# BrushlessLampRoutes.net
KiCad netlist of a schematic drawn in EAGLE
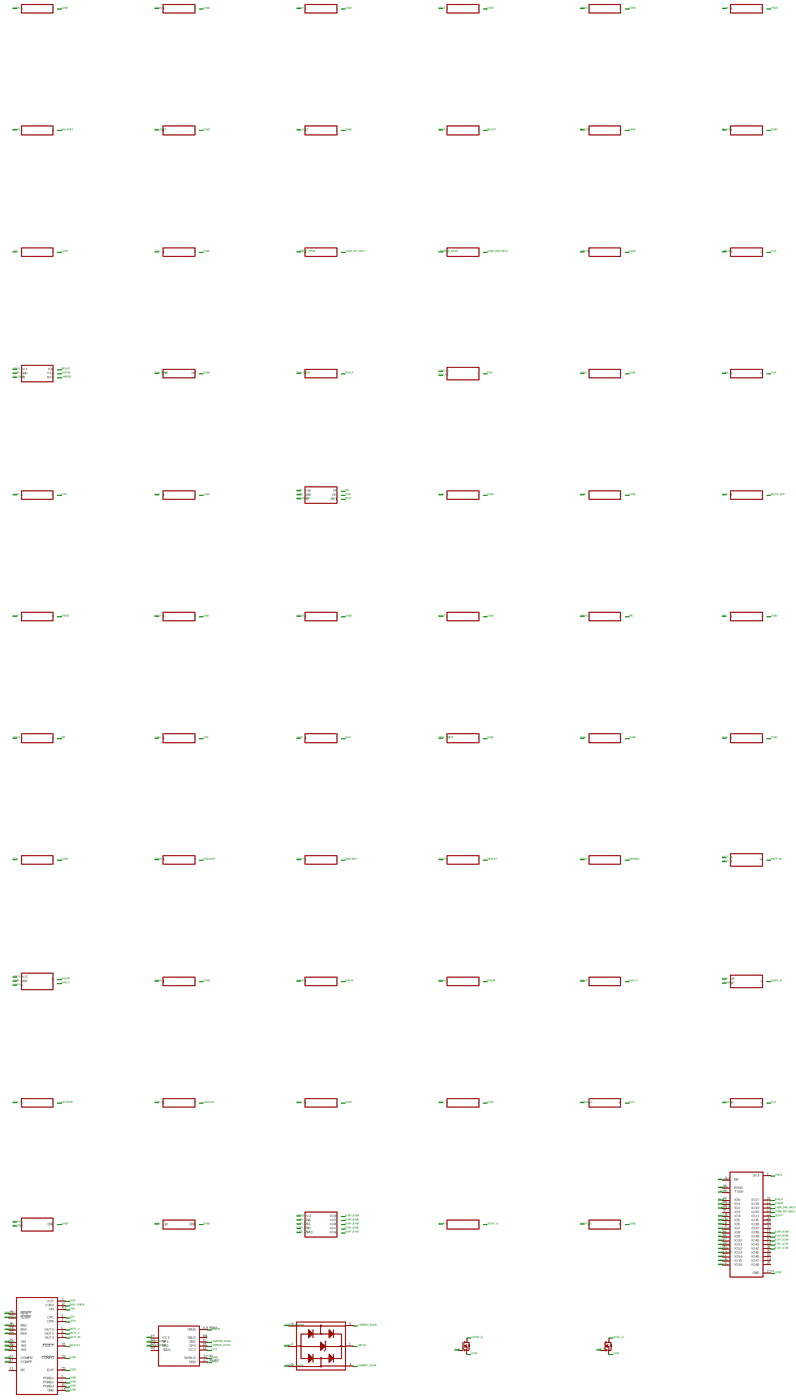
[diagram p0: schematic, sheet 1, overview]
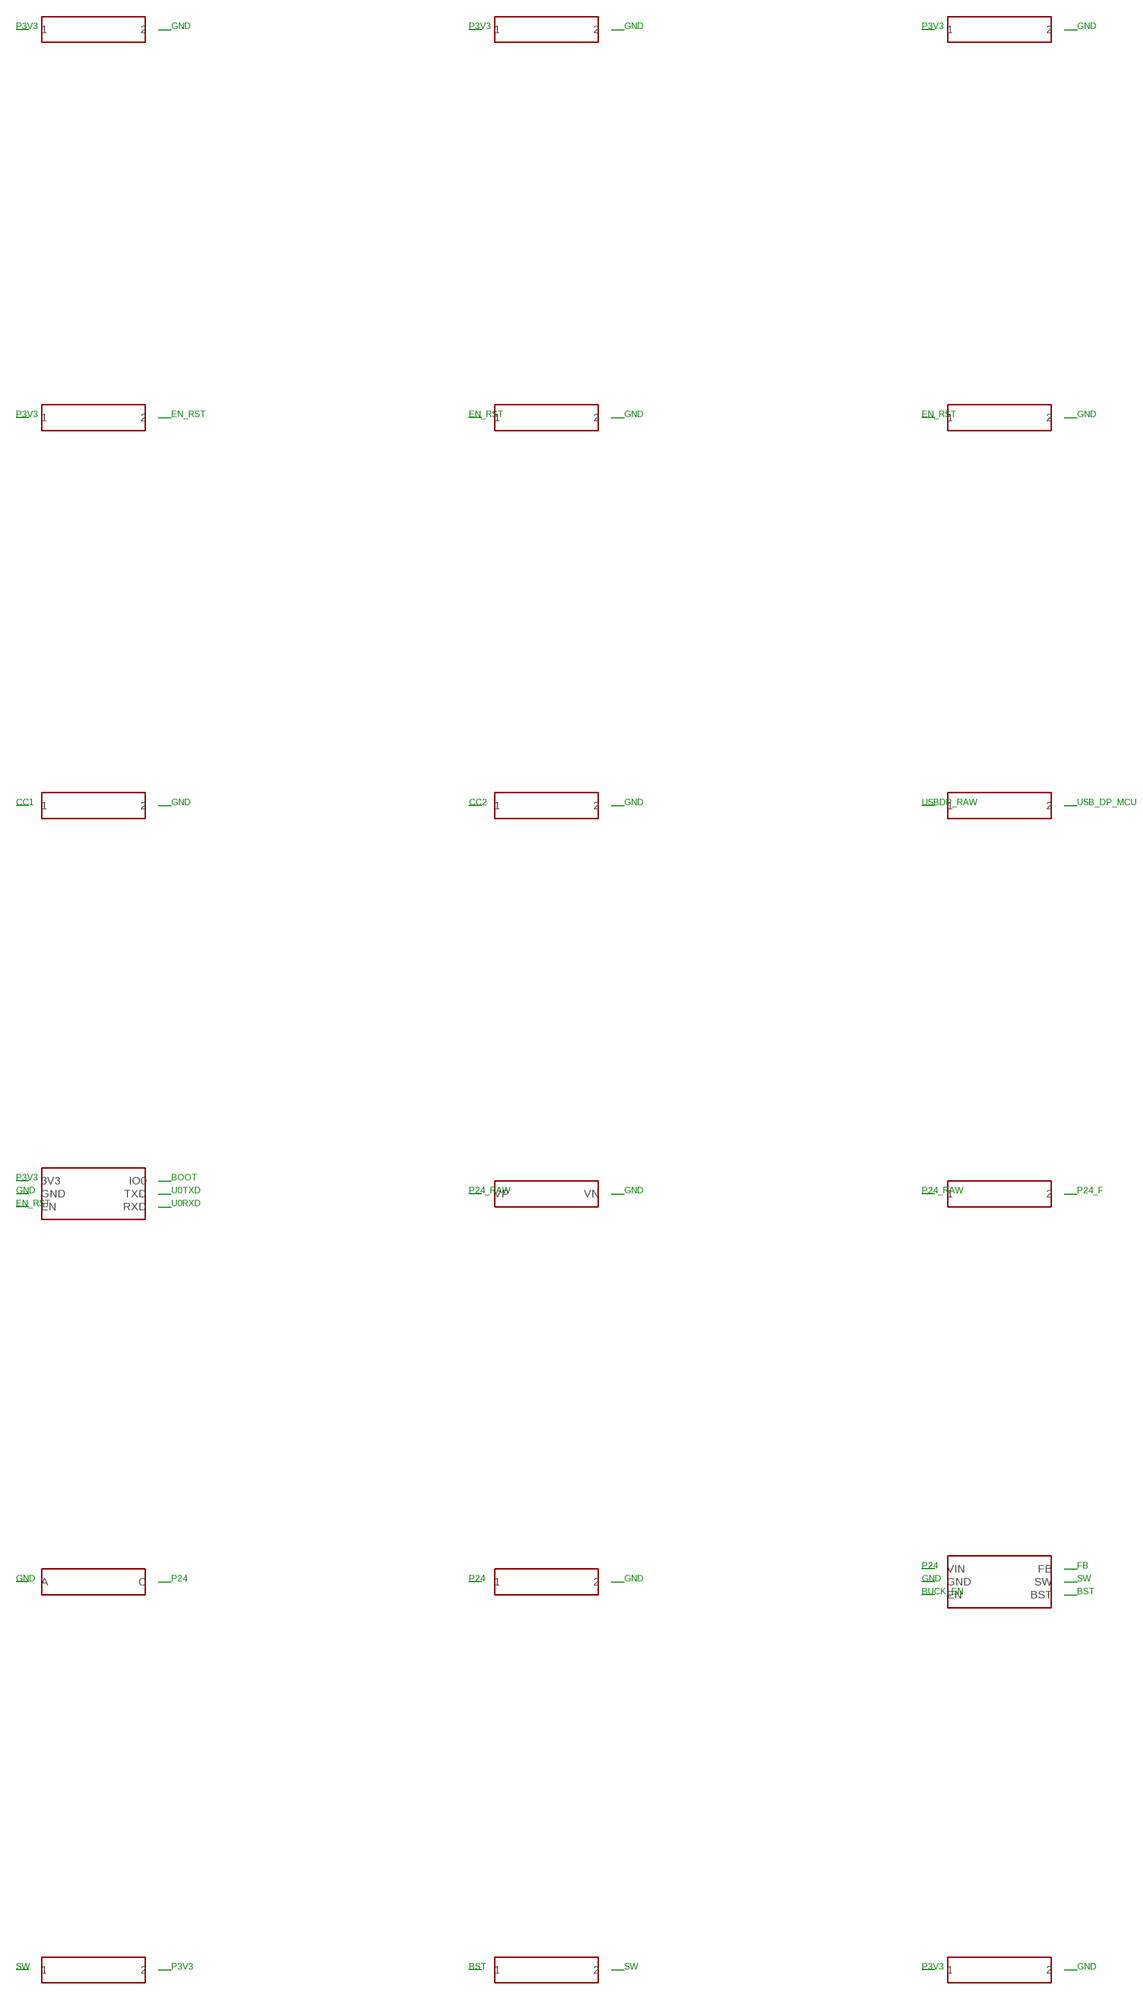
[diagram p1: schematic, sheet 1, part 1 of 4]
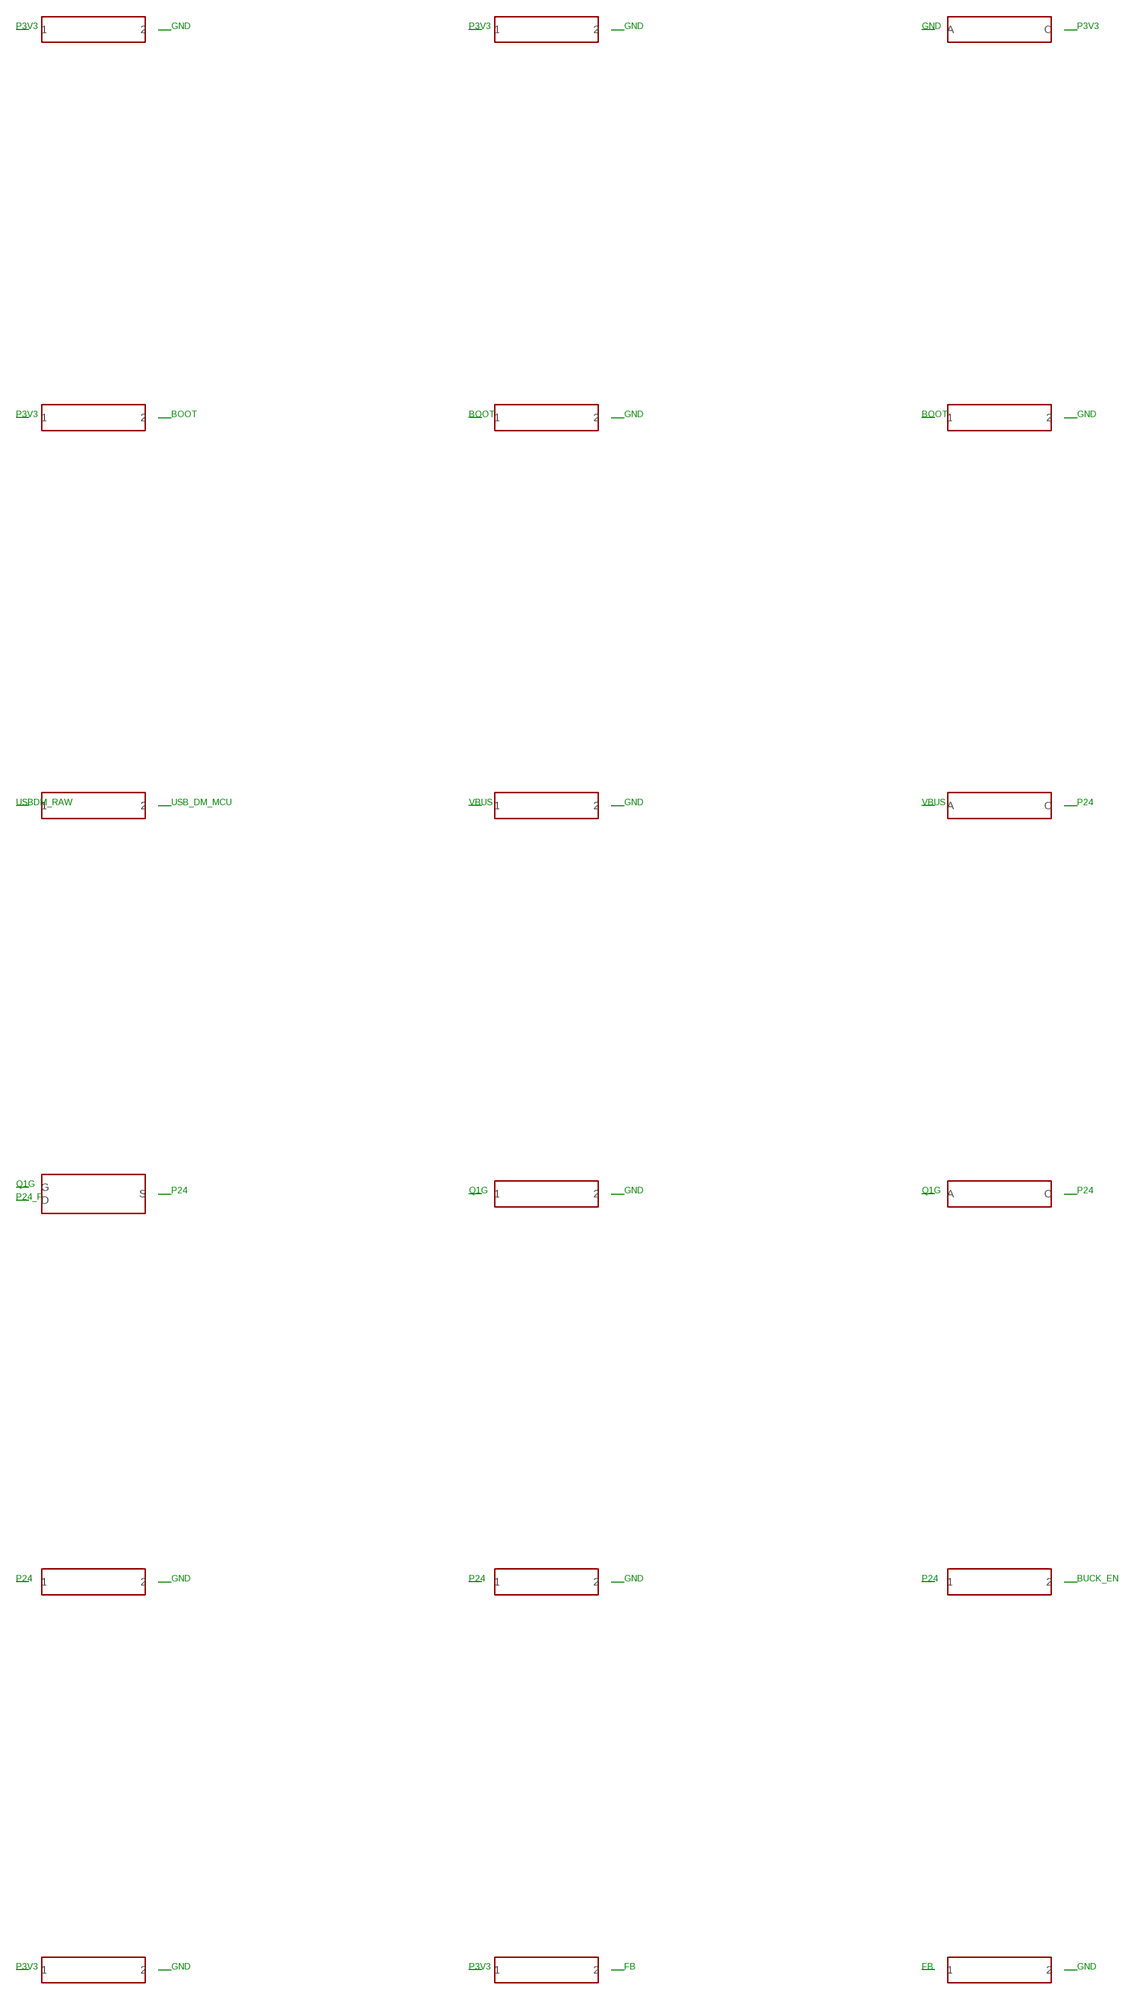
[diagram p2: schematic, sheet 1, part 2 of 4]
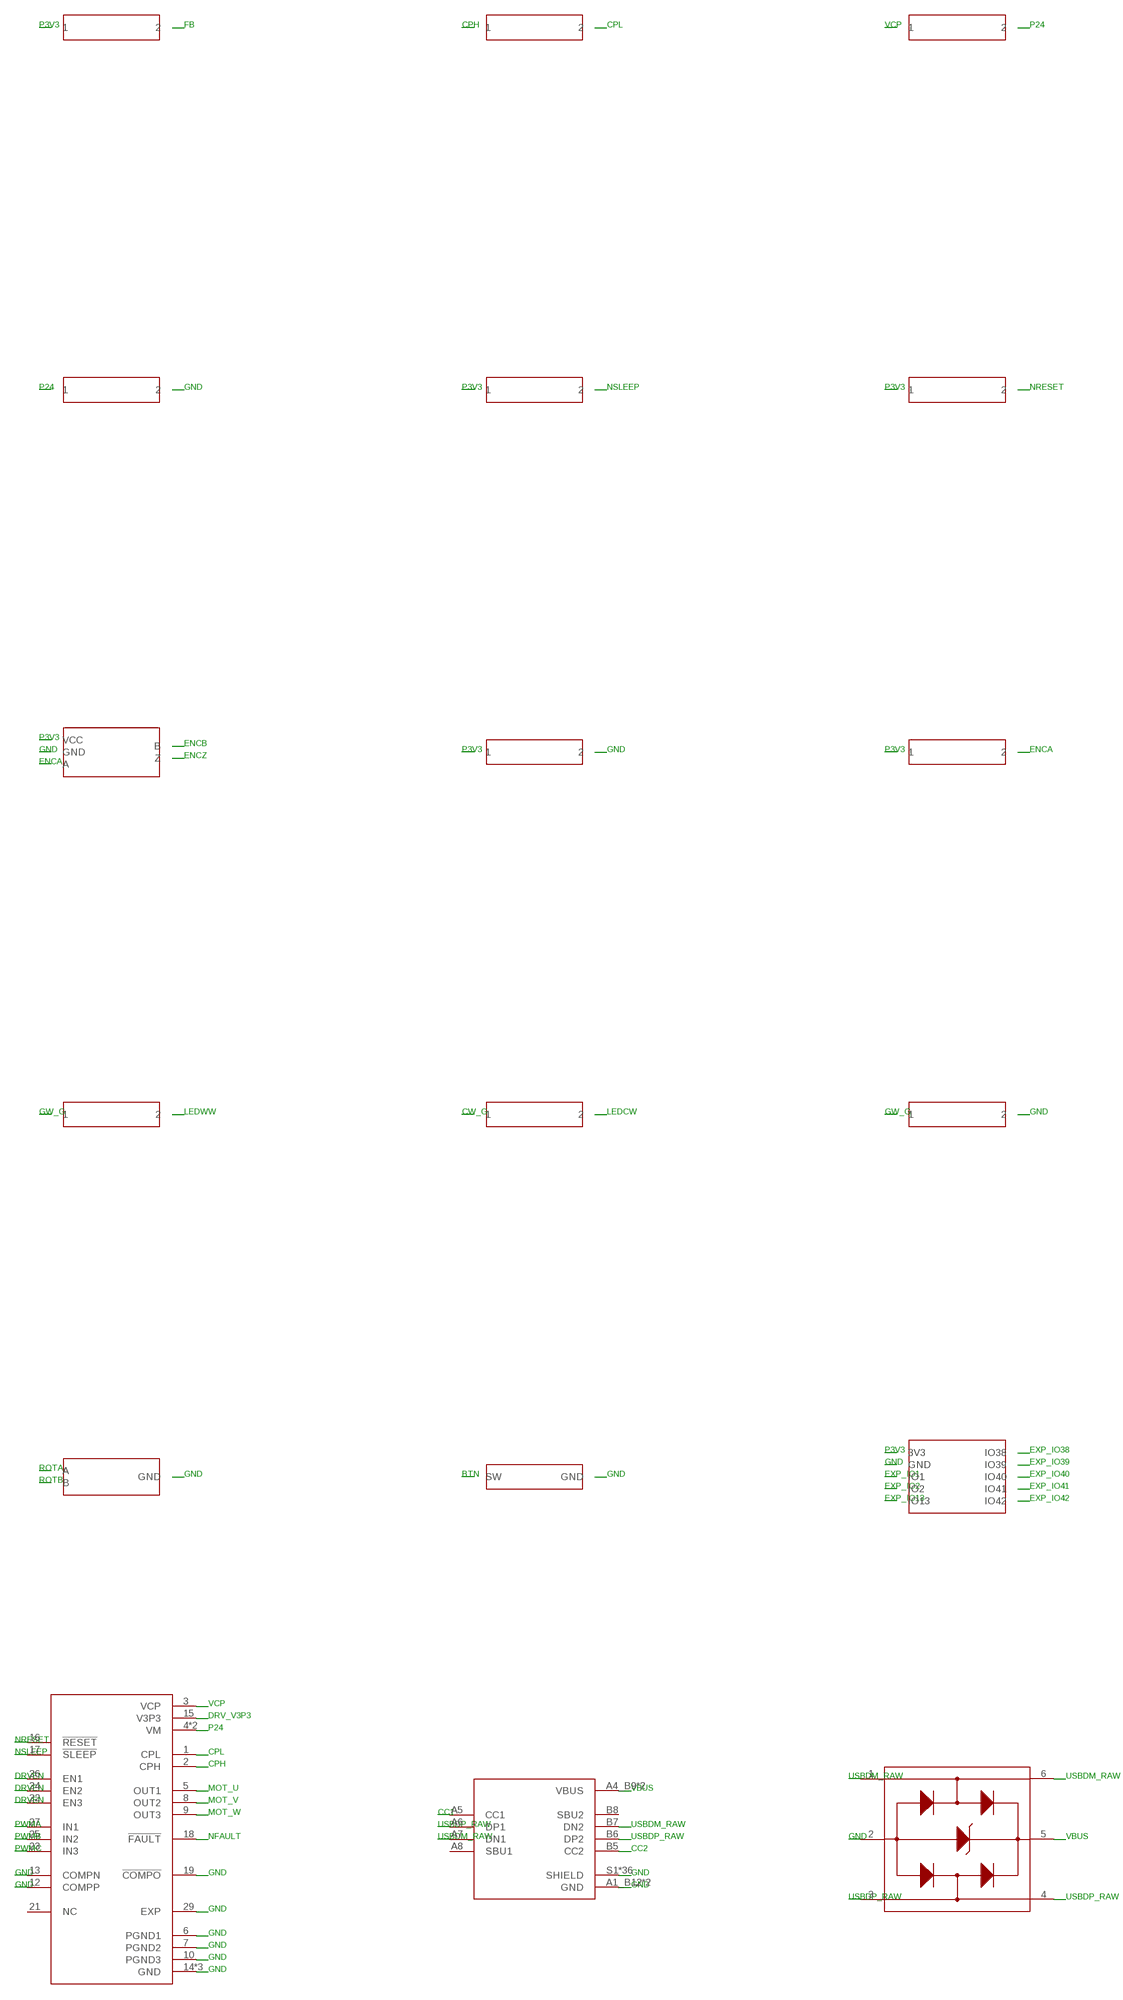
[diagram p3: schematic, sheet 1, part 3 of 4]
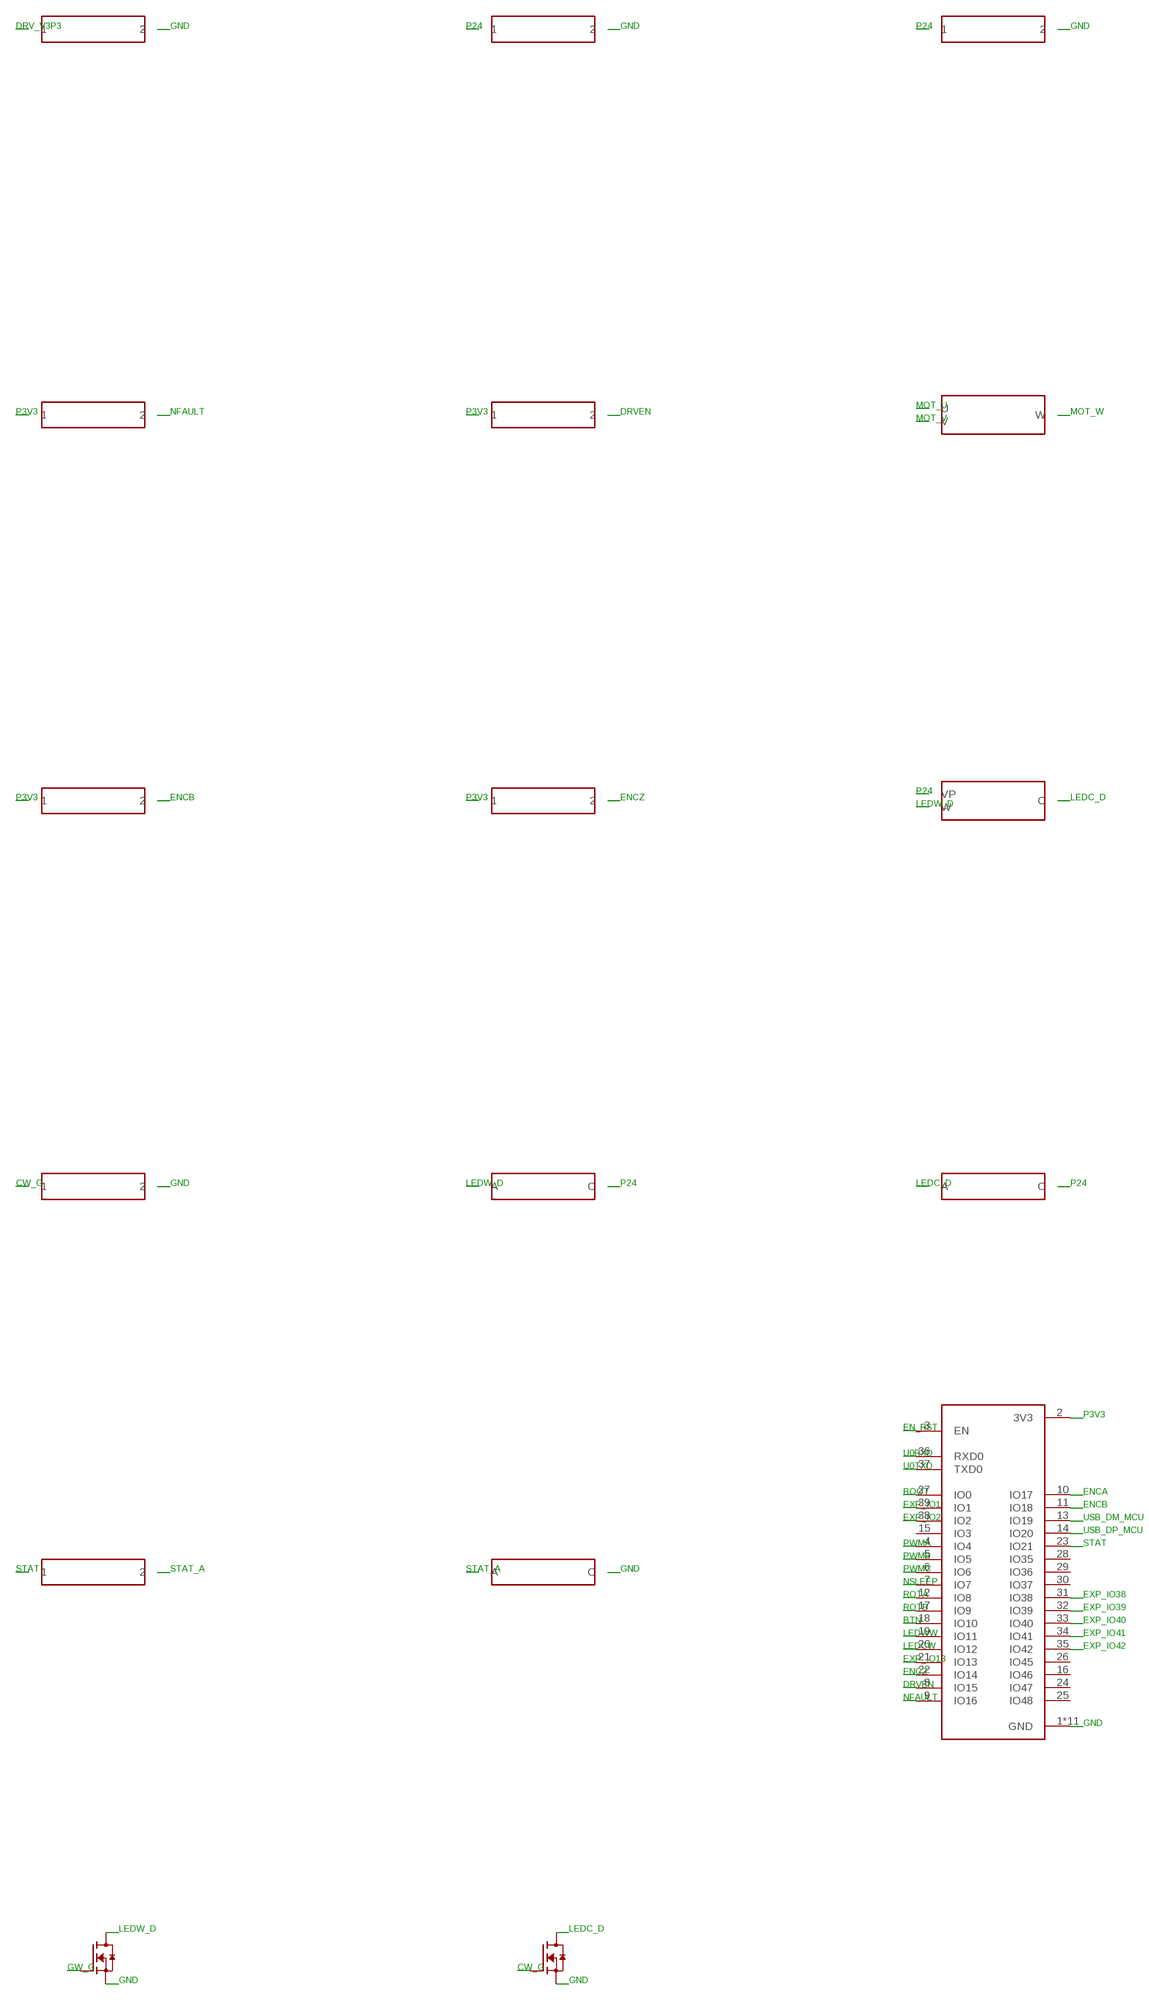
[diagram p4: schematic, sheet 1, part 4 of 4]

(export (version "E")
  (design (tool "Eeschema 10.0.6"))
  (components
    (comp (ref "C_BOOT")
      (value "100p")
      (footprint "eagle-import:0402")
      (libsource (lib "eagle-import") (part "CAP_0402"))
    )
    (comp (ref "C_BOOT_B")
      (value "100n")
      (footprint "eagle-import:0402")
      (libsource (lib "eagle-import") (part "CAP_0402"))
    )
    (comp (ref "C_CP")
      (value "10n")
      (footprint "eagle-import:0603")
      (libsource (lib "eagle-import") (part "CAP_0603"))
    )
    (comp (ref "C_EN")
      (value "1u")
      (footprint "eagle-import:0603")
      (libsource (lib "eagle-import") (part "CAP_0603"))
    )
    (comp (ref "C_FF")
      (value "22p")
      (footprint "eagle-import:0402")
      (libsource (lib "eagle-import") (part "CAP_0402"))
    )
    (comp (ref "C_IN1")
      (value "10u-50V")
      (footprint "eagle-import:1210")
      (libsource (lib "eagle-import") (part "CAP_1210"))
    )
    (comp (ref "C_IN2")
      (value "4.7u-50V")
      (footprint "eagle-import:1206")
      (libsource (lib "eagle-import") (part "CAP_1206"))
    )
    (comp (ref "C_IN_BULK")
      (value "100u-50V")
      (footprint "eagle-import:CAP_V")
      (libsource (lib "eagle-import") (part "CAP_V"))
    )
    (comp (ref "C_MCU1")
      (value "10u")
      (footprint "eagle-import:0805")
      (libsource (lib "eagle-import") (part "CAP_0805"))
    )
    (comp (ref "C_MCU2")
      (value "1u")
      (footprint "eagle-import:0603")
      (libsource (lib "eagle-import") (part "CAP_0603"))
    )
    (comp (ref "C_MCU3")
      (value "100n")
      (footprint "eagle-import:0402")
      (libsource (lib "eagle-import") (part "CAP_0402"))
    )
    (comp (ref "C_MCU4")
      (value "100n")
      (footprint "eagle-import:0402")
      (libsource (lib "eagle-import") (part "CAP_0402"))
    )
    (comp (ref "C_MCU_BULK")
      (value "470u")
      (footprint "eagle-import:CAP_D")
      (libsource (lib "eagle-import") (part "CAP_D"))
    )
    (comp (ref "C_OUT1")
      (value "22u")
      (footprint "eagle-import:0805")
      (libsource (lib "eagle-import") (part "CAP_0805"))
    )
    (comp (ref "C_OUT2")
      (value "22u")
      (footprint "eagle-import:0805")
      (libsource (lib "eagle-import") (part "CAP_0805"))
    )
    (comp (ref "C_SENS")
      (value "100n")
      (footprint "eagle-import:0402")
      (libsource (lib "eagle-import") (part "CAP_0402"))
    )
    (comp (ref "C_V3P3")
      (value "470n")
      (footprint "eagle-import:0603")
      (libsource (lib "eagle-import") (part "CAP_0603"))
    )
    (comp (ref "C_VBUS")
      (value "4.7u")
      (footprint "eagle-import:0603")
      (libsource (lib "eagle-import") (part "CAP_0603"))
    )
    (comp (ref "C_VCP")
      (value "100n")
      (footprint "eagle-import:0603")
      (libsource (lib "eagle-import") (part "CAP_0603"))
    )
    (comp (ref "C_VM1")
      (value "100n-50V")
      (footprint "eagle-import:0603")
      (libsource (lib "eagle-import") (part "CAP_0603"))
    )
    (comp (ref "C_VM2")
      (value "100n-50V")
      (footprint "eagle-import:0603")
      (libsource (lib "eagle-import") (part "CAP_0603"))
    )
    (comp (ref "C_VM_BULK")
      (value "100u-50V")
      (footprint "eagle-import:CAP_V")
      (libsource (lib "eagle-import") (part "CAP_V"))
    )
    (comp (ref "D_CLC")
      (value "clamp-DNP")
      (footprint "eagle-import:SOD323")
      (libsource (lib "eagle-import") (part "DIODE_SOD323"))
    )
    (comp (ref "D_CLW")
      (value "clamp-DNP")
      (footprint "eagle-import:SOD323")
      (libsource (lib "eagle-import") (part "DIODE_SOD323"))
    )
    (comp (ref "D_MCU")
      (value "ESD")
      (footprint "eagle-import:SOD323")
      (libsource (lib "eagle-import") (part "DIODE_SOD323"))
    )
    (comp (ref "D_OR_USB")
      (value "SS14")
      (footprint "eagle-import:SMA")
      (libsource (lib "eagle-import") (part "DIODE_SMA"))
    )
    (comp (ref "D_Q1")
      (value "10V-Zener")
      (footprint "eagle-import:SOD123")
      (libsource (lib "eagle-import") (part "DIODE_SOD123"))
    )
    (comp (ref "D_USB")
      (value "USBLC6-2SC6")
      (footprint "eagle-import:SOT95P280X145-6N")
      (fields (field (name "MF") "STMicroelectronics"))
      (libsource (lib "eagle-import") (part "USBLC6-2SC6"))
    )
    (comp (ref "F1")
      (value "2A")
      (footprint "eagle-import:FUSENANO2")
      (libsource (lib "eagle-import") (part "FUSE_NANO2"))
    )
    (comp (ref "J_BTN")
      (value "BUTTON")
      (footprint "eagle-import:XH2")
      (libsource (lib "eagle-import") (part "CONN_BTN_DS"))
    )
    (comp (ref "J_EXP")
      (value "GPIO-EXP")
      (footprint "eagle-import:HDR10")
      (libsource (lib "eagle-import") (part "CONN_EXP_DS"))
    )
    (comp (ref "J_KNOB")
      (value "KNOB")
      (footprint "eagle-import:XH3")
      (libsource (lib "eagle-import") (part "CONN_KNOB_DS"))
    )
    (comp (ref "J_LED")
      (value "CCT-STRIP")
      (footprint "eagle-import:XH3")
      (libsource (lib "eagle-import") (part "CONN_LED_DS"))
    )
    (comp (ref "J_MOTOR")
      (value "MOTOR")
      (footprint "eagle-import:SCREW3")
      (libsource (lib "eagle-import") (part "CONN_MOTOR_DS"))
    )
    (comp (ref "J_PROG")
      (value "UART-FALLBACK")
      (footprint "eagle-import:HDR6")
      (libsource (lib "eagle-import") (part "CONN_PROG_DS"))
    )
    (comp (ref "J_PWR")
      (value "24V-IN")
      (footprint "eagle-import:SCREW2")
      (libsource (lib "eagle-import") (part "CONN_PWR_DS"))
    )
    (comp (ref "J_SENSOR")
      (value "MT6701")
      (footprint "eagle-import:SCREW5")
      (libsource (lib "eagle-import") (part "CONN_SENSOR_DS"))
    )
    (comp (ref "J_USB")
      (value "TYPE-C-31-M-12")
      (footprint "eagle-import:HRO_TYPE-C-31-M-12")
      (fields (field (name "MF") "HRO Electronics Co., Ltd."))
      (libsource (lib "eagle-import") (part "TYPE-C-31-M-12"))
    )
    (comp (ref "L1")
      (value "4.7uH")
      (footprint "eagle-import:IND43")
      (libsource (lib "eagle-import") (part "IND_SMD"))
    )
    (comp (ref "LED_STATUS")
      (value "STATUS")
      (footprint "eagle-import:LED0603")
      (libsource (lib "eagle-import") (part "LED_0603"))
    )
    (comp (ref "Q1")
      (value "PMOS-RevProt")
      (footprint "eagle-import:SOT23")
      (libsource (lib "eagle-import") (part "FET_SOT23"))
    )
    (comp (ref "Q_CW")
      (value "AO3400A")
      (footprint "eagle-import:SOT95P280X125-3N")
      (fields (field (name "MF") "UMW"))
      (libsource (lib "eagle-import") (part "AO3400A"))
    )
    (comp (ref "Q_WW")
      (value "AO3400A")
      (footprint "eagle-import:SOT95P280X125-3N")
      (fields (field (name "MF") "UMW"))
      (libsource (lib "eagle-import") (part "AO3400A"))
    )
    (comp (ref "R_AZ_A")
      (value "10k-DNP")
      (footprint "eagle-import:0603")
      (libsource (lib "eagle-import") (part "RES_0603"))
    )
    (comp (ref "R_AZ_B")
      (value "10k-DNP")
      (footprint "eagle-import:0603")
      (libsource (lib "eagle-import") (part "RES_0603"))
    )
    (comp (ref "R_AZ_C")
      (value "10k-DNP")
      (footprint "eagle-import:0603")
      (libsource (lib "eagle-import") (part "RES_0603"))
    )
    (comp (ref "R_BOOT")
      (value "10k")
      (footprint "eagle-import:0603")
      (libsource (lib "eagle-import") (part "RES_0603"))
    )
    (comp (ref "R_CC1")
      (value "5.1k")
      (footprint "eagle-import:0603")
      (libsource (lib "eagle-import") (part "RES_0603"))
    )
    (comp (ref "R_CC2")
      (value "5.1k")
      (footprint "eagle-import:0603")
      (libsource (lib "eagle-import") (part "RES_0603"))
    )
    (comp (ref "R_DM")
      (value "22R")
      (footprint "eagle-import:0603")
      (libsource (lib "eagle-import") (part "RES_0603"))
    )
    (comp (ref "R_DP")
      (value "22R")
      (footprint "eagle-import:0603")
      (libsource (lib "eagle-import") (part "RES_0603"))
    )
    (comp (ref "R_EN")
      (value "10k")
      (footprint "eagle-import:0603")
      (libsource (lib "eagle-import") (part "RES_0603"))
    )
    (comp (ref "R_ENB")
      (value "100k")
      (footprint "eagle-import:0603")
      (libsource (lib "eagle-import") (part "RES_0603"))
    )
    (comp (ref "R_EN_DRV")
      (value "10k")
      (footprint "eagle-import:0603")
      (libsource (lib "eagle-import") (part "RES_0603"))
    )
    (comp (ref "R_FBB")
      (value "10k")
      (footprint "eagle-import:0603")
      (libsource (lib "eagle-import") (part "RES_0603"))
    )
    (comp (ref "R_FBT")
      (value "45.3k")
      (footprint "eagle-import:0603")
      (libsource (lib "eagle-import") (part "RES_0603"))
    )
    (comp (ref "R_GC")
      (value "33R")
      (footprint "eagle-import:0603")
      (libsource (lib "eagle-import") (part "RES_0603"))
    )
    (comp (ref "R_GW")
      (value "33R")
      (footprint "eagle-import:0603")
      (libsource (lib "eagle-import") (part "RES_0603"))
    )
    (comp (ref "R_NFAULT")
      (value "10k")
      (footprint "eagle-import:0603")
      (libsource (lib "eagle-import") (part "RES_0603"))
    )
    (comp (ref "R_NRESET")
      (value "10k")
      (footprint "eagle-import:0603")
      (libsource (lib "eagle-import") (part "RES_0603"))
    )
    (comp (ref "R_NSLEEP")
      (value "10k")
      (footprint "eagle-import:0603")
      (libsource (lib "eagle-import") (part "RES_0603"))
    )
    (comp (ref "R_PDC")
      (value "100k")
      (footprint "eagle-import:0603")
      (libsource (lib "eagle-import") (part "RES_0603"))
    )
    (comp (ref "R_PDW")
      (value "100k")
      (footprint "eagle-import:0603")
      (libsource (lib "eagle-import") (part "RES_0603"))
    )
    (comp (ref "R_Q1")
      (value "100k")
      (footprint "eagle-import:0603")
      (libsource (lib "eagle-import") (part "RES_0603"))
    )
    (comp (ref "R_STATUS")
      (value "1k")
      (footprint "eagle-import:0603")
      (libsource (lib "eagle-import") (part "RES_0603"))
    )
    (comp (ref "SW_BOOT")
      (value "BOOT")
      (footprint "eagle-import:TACT")
      (libsource (lib "eagle-import") (part "SW_TACT"))
    )
    (comp (ref "SW_RST")
      (value "RESET")
      (footprint "eagle-import:TACT")
      (libsource (lib "eagle-import") (part "SW_TACT"))
    )
    (comp (ref "TVS1")
      (value "SMBJ28A")
      (footprint "eagle-import:SMB")
      (libsource (lib "eagle-import") (part "DIODE_SMB"))
    )
    (comp (ref "U_BUCK")
      (value "LMR51430")
      (footprint "eagle-import:SOT236")
      (libsource (lib "eagle-import") (part "BUCK_DS"))
    )
    (comp (ref "U_DRV")
      (value "DRV8313PWPR")
      (footprint "eagle-import:SOP65P640X120-29N")
      (fields (field (name "MF") "Texas Instruments"))
      (libsource (lib "eagle-import") (part "DRV8313PWPR"))
    )
    (comp (ref "U_MCU")
      (value "ESP32-S3-WROOM-1-N8R8")
      (footprint "eagle-import:XCVR_ESP32S3WROOM1N8R8")
      (fields (field (name "MF") "Espressif Systems"))
      (libsource (lib "eagle-import") (part "ESP32-S3-WROOM-1-N8R8"))
    )
  )
  (nets
    (net (code "1") (name "/BOOT") (class "Default")
      (node (ref "C_BOOT") (pin "1") (pinfunction "1_1") (pintype "passive"))
      (node (ref "J_PROG") (pin "4") (pinfunction "IO0_4") (pintype "passive"))
      (node (ref "R_BOOT") (pin "2") (pinfunction "2_2") (pintype "passive"))
      (node (ref "SW_BOOT") (pin "1") (pinfunction "1_1") (pintype "passive"))
      (node (ref "SW_BOOT") (pin "2") (pinfunction "1_2") (pintype "passive"))
      (node (ref "U_MCU") (pin "27") (pinfunction "IO0_27") (pintype "bidirectional"))
    )
    (net (code "2") (name "/BST") (class "Default")
      (node (ref "C_BOOT_B") (pin "1") (pinfunction "1_1") (pintype "passive"))
      (node (ref "U_BUCK") (pin "6") (pinfunction "BST_6") (pintype "passive"))
    )
    (net (code "3") (name "/BTN") (class "Default")
      (node (ref "J_BTN") (pin "1") (pinfunction "SW_1") (pintype "passive"))
      (node (ref "U_MCU") (pin "18") (pinfunction "IO10_18") (pintype "bidirectional"))
    )
    (net (code "4") (name "/BUCK_EN") (class "Default")
      (node (ref "R_ENB") (pin "2") (pinfunction "2_2") (pintype "passive"))
      (node (ref "U_BUCK") (pin "5") (pinfunction "EN_5") (pintype "passive"))
    )
    (net (code "5") (name "/CC1") (class "Default")
      (node (ref "J_USB") (pin "A5") (pinfunction "CC1_A5") (pintype "bidirectional"))
      (node (ref "R_CC1") (pin "1") (pinfunction "1_1") (pintype "passive"))
    )
    (net (code "6") (name "/CC2") (class "Default")
      (node (ref "J_USB") (pin "B5") (pinfunction "CC2_B5") (pintype "bidirectional"))
      (node (ref "R_CC2") (pin "1") (pinfunction "1_1") (pintype "passive"))
    )
    (net (code "7") (name "/CPH") (class "Default")
      (node (ref "C_CP") (pin "1") (pinfunction "1_1") (pintype "passive"))
      (node (ref "U_DRV") (pin "2") (pinfunction "CPH_2") (pintype "power_in"))
    )
    (net (code "8") (name "/CPL") (class "Default")
      (node (ref "C_CP") (pin "2") (pinfunction "2_2") (pintype "passive"))
      (node (ref "U_DRV") (pin "1") (pinfunction "CPL_1") (pintype "power_in"))
    )
    (net (code "9") (name "/CW_G") (class "Default")
      (node (ref "Q_CW") (pin "1") (pinfunction "G_1") (pintype "passive"))
      (node (ref "R_GC") (pin "1") (pinfunction "1_1") (pintype "passive"))
      (node (ref "R_PDC") (pin "1") (pinfunction "1_1") (pintype "passive"))
    )
    (net (code "10") (name "/DRVEN") (class "Default")
      (node (ref "R_EN_DRV") (pin "2") (pinfunction "2_2") (pintype "passive"))
      (node (ref "U_DRV") (pin "22") (pinfunction "EN3_22") (pintype "input"))
      (node (ref "U_DRV") (pin "24") (pinfunction "EN2_24") (pintype "input"))
      (node (ref "U_DRV") (pin "26") (pinfunction "EN1_26") (pintype "input"))
      (node (ref "U_MCU") (pin "8") (pinfunction "IO15_8") (pintype "bidirectional"))
    )
    (net (code "11") (name "/DRV_V3P3") (class "Default")
      (node (ref "C_V3P3") (pin "1") (pinfunction "1_1") (pintype "passive"))
      (node (ref "U_DRV") (pin "15") (pinfunction "V3P3_15") (pintype "power_in"))
    )
    (net (code "12") (name "/ENCA") (class "Default")
      (node (ref "J_SENSOR") (pin "3") (pinfunction "A_3") (pintype "passive"))
      (node (ref "R_AZ_A") (pin "2") (pinfunction "2_2") (pintype "passive"))
      (node (ref "U_MCU") (pin "10") (pinfunction "IO17_10") (pintype "bidirectional"))
    )
    (net (code "13") (name "/ENCB") (class "Default")
      (node (ref "J_SENSOR") (pin "4") (pinfunction "B_4") (pintype "passive"))
      (node (ref "R_AZ_B") (pin "2") (pinfunction "2_2") (pintype "passive"))
      (node (ref "U_MCU") (pin "11") (pinfunction "IO18_11") (pintype "bidirectional"))
    )
    (net (code "14") (name "/ENCZ") (class "Default")
      (node (ref "J_SENSOR") (pin "5") (pinfunction "Z_5") (pintype "passive"))
      (node (ref "R_AZ_C") (pin "2") (pinfunction "2_2") (pintype "passive"))
      (node (ref "U_MCU") (pin "22") (pinfunction "IO14_22") (pintype "bidirectional"))
    )
    (net (code "15") (name "/EN_RST") (class "Default")
      (node (ref "C_EN") (pin "1") (pinfunction "1_1") (pintype "passive"))
      (node (ref "J_PROG") (pin "3") (pinfunction "EN_3") (pintype "passive"))
      (node (ref "R_EN") (pin "2") (pinfunction "2_2") (pintype "passive"))
      (node (ref "SW_RST") (pin "1") (pinfunction "1_1") (pintype "passive"))
      (node (ref "SW_RST") (pin "2") (pinfunction "1_2") (pintype "passive"))
      (node (ref "U_MCU") (pin "3") (pinfunction "EN_3") (pintype "input"))
    )
    (net (code "16") (name "/EXP_IO1") (class "Default")
      (node (ref "J_EXP") (pin "3") (pinfunction "IO1_3") (pintype "passive"))
      (node (ref "U_MCU") (pin "39") (pinfunction "IO1_39") (pintype "bidirectional"))
    )
    (net (code "17") (name "/EXP_IO2") (class "Default")
      (node (ref "J_EXP") (pin "4") (pinfunction "IO2_4") (pintype "passive"))
      (node (ref "U_MCU") (pin "38") (pinfunction "IO2_38") (pintype "bidirectional"))
    )
    (net (code "18") (name "/EXP_IO13") (class "Default")
      (node (ref "J_EXP") (pin "5") (pinfunction "IO13_5") (pintype "passive"))
      (node (ref "U_MCU") (pin "21") (pinfunction "IO13_21") (pintype "bidirectional"))
    )
    (net (code "19") (name "/EXP_IO38") (class "Default")
      (node (ref "J_EXP") (pin "6") (pinfunction "IO38_6") (pintype "passive"))
      (node (ref "U_MCU") (pin "31") (pinfunction "IO38_31") (pintype "bidirectional"))
    )
    (net (code "20") (name "/EXP_IO39") (class "Default")
      (node (ref "J_EXP") (pin "7") (pinfunction "IO39_7") (pintype "passive"))
      (node (ref "U_MCU") (pin "32") (pinfunction "IO39_32") (pintype "bidirectional"))
    )
    (net (code "21") (name "/EXP_IO40") (class "Default")
      (node (ref "J_EXP") (pin "8") (pinfunction "IO40_8") (pintype "passive"))
      (node (ref "U_MCU") (pin "33") (pinfunction "IO40_33") (pintype "bidirectional"))
    )
    (net (code "22") (name "/EXP_IO41") (class "Default")
      (node (ref "J_EXP") (pin "9") (pinfunction "IO41_9") (pintype "passive"))
      (node (ref "U_MCU") (pin "34") (pinfunction "IO41_34") (pintype "bidirectional"))
    )
    (net (code "23") (name "/EXP_IO42") (class "Default")
      (node (ref "J_EXP") (pin "10") (pinfunction "IO42_10") (pintype "passive"))
      (node (ref "U_MCU") (pin "35") (pinfunction "IO42_35") (pintype "bidirectional"))
    )
    (net (code "24") (name "/FB") (class "Default")
      (node (ref "C_FF") (pin "2") (pinfunction "2_2") (pintype "passive"))
      (node (ref "R_FBB") (pin "1") (pinfunction "1_1") (pintype "passive"))
      (node (ref "R_FBT") (pin "2") (pinfunction "2_2") (pintype "passive"))
      (node (ref "U_BUCK") (pin "4") (pinfunction "FB_4") (pintype "passive"))
    )
    (net (code "25") (name "/GND") (class "Default")
      (node (ref "C_BOOT") (pin "2") (pinfunction "2_2") (pintype "passive"))
      (node (ref "C_EN") (pin "2") (pinfunction "2_2") (pintype "passive"))
      (node (ref "C_IN1") (pin "2") (pinfunction "2_2") (pintype "passive"))
      (node (ref "C_IN2") (pin "2") (pinfunction "2_2") (pintype "passive"))
      (node (ref "C_IN_BULK") (pin "2") (pinfunction "2_2") (pintype "passive"))
      (node (ref "C_MCU1") (pin "2") (pinfunction "2_2") (pintype "passive"))
      (node (ref "C_MCU2") (pin "2") (pinfunction "2_2") (pintype "passive"))
      (node (ref "C_MCU3") (pin "2") (pinfunction "2_2") (pintype "passive"))
      (node (ref "C_MCU4") (pin "2") (pinfunction "2_2") (pintype "passive"))
      (node (ref "C_MCU_BULK") (pin "2") (pinfunction "2_2") (pintype "passive"))
      (node (ref "C_OUT1") (pin "2") (pinfunction "2_2") (pintype "passive"))
      (node (ref "C_OUT2") (pin "2") (pinfunction "2_2") (pintype "passive"))
      (node (ref "C_SENS") (pin "2") (pinfunction "2_2") (pintype "passive"))
      (node (ref "C_V3P3") (pin "2") (pinfunction "2_2") (pintype "passive"))
      (node (ref "C_VBUS") (pin "2") (pinfunction "2_2") (pintype "passive"))
      (node (ref "C_VM1") (pin "2") (pinfunction "2_2") (pintype "passive"))
      (node (ref "C_VM2") (pin "2") (pinfunction "2_2") (pintype "passive"))
      (node (ref "C_VM_BULK") (pin "2") (pinfunction "2_2") (pintype "passive"))
      (node (ref "D_MCU") (pin "A") (pinfunction "A_A") (pintype "passive"))
      (node (ref "D_USB") (pin "2") (pinfunction "GND_2") (pintype "power_in"))
      (node (ref "J_BTN") (pin "2") (pinfunction "GND_2") (pintype "passive"))
      (node (ref "J_EXP") (pin "2") (pinfunction "GND_2") (pintype "passive"))
      (node (ref "J_KNOB") (pin "3") (pinfunction "GND_3") (pintype "passive"))
      (node (ref "J_PROG") (pin "2") (pinfunction "GND_2") (pintype "passive"))
      (node (ref "J_PWR") (pin "2") (pinfunction "VN_2") (pintype "passive"))
      (node (ref "J_SENSOR") (pin "2") (pinfunction "GND_2") (pintype "passive"))
      (node (ref "J_USB") (pin "A1_B12") (pinfunction "GND_A1_B12") (pintype "power_in"))
      (node (ref "J_USB") (pin "B1_A12") (pinfunction "GND_B1_A12") (pintype "power_in"))
      (node (ref "J_USB") (pin "S1") (pinfunction "SHIELD_S1") (pintype "passive"))
      (node (ref "J_USB") (pin "S1B") (pinfunction "SHIELD_S1B") (pintype "passive"))
      (node (ref "J_USB") (pin "S1C") (pinfunction "SHIELD_S1C") (pintype "passive"))
      (node (ref "J_USB") (pin "S1D") (pinfunction "SHIELD_S1D") (pintype "passive"))
      (node (ref "J_USB") (pin "S1E") (pinfunction "SHIELD_S1E") (pintype "passive"))
      (node (ref "J_USB") (pin "S1F") (pinfunction "SHIELD_S1F") (pintype "passive"))
      (node (ref "J_USB") (pin "S1G") (pinfunction "SHIELD_S1G") (pintype "passive"))
      (node (ref "J_USB") (pin "S1H") (pinfunction "SHIELD_S1H") (pintype "passive"))
      (node (ref "J_USB") (pin "S1I") (pinfunction "SHIELD_S1I") (pintype "passive"))
      (node (ref "J_USB") (pin "S2") (pinfunction "SHIELD_S2") (pintype "passive"))
      (node (ref "J_USB") (pin "S2B") (pinfunction "SHIELD_S2B") (pintype "passive"))
      (node (ref "J_USB") (pin "S2C") (pinfunction "SHIELD_S2C") (pintype "passive"))
      (node (ref "J_USB") (pin "S2D") (pinfunction "SHIELD_S2D") (pintype "passive"))
      (node (ref "J_USB") (pin "S2E") (pinfunction "SHIELD_S2E") (pintype "passive"))
      (node (ref "J_USB") (pin "S2F") (pinfunction "SHIELD_S2F") (pintype "passive"))
      (node (ref "J_USB") (pin "S2G") (pinfunction "SHIELD_S2G") (pintype "passive"))
      (node (ref "J_USB") (pin "S2H") (pinfunction "SHIELD_S2H") (pintype "passive"))
      (node (ref "J_USB") (pin "S2I") (pinfunction "SHIELD_S2I") (pintype "passive"))
      (node (ref "J_USB") (pin "S3") (pinfunction "SHIELD_S3") (pintype "passive"))
      (node (ref "J_USB") (pin "S3B") (pinfunction "SHIELD_S3B") (pintype "passive"))
      (node (ref "J_USB") (pin "S3C") (pinfunction "SHIELD_S3C") (pintype "passive"))
      (node (ref "J_USB") (pin "S3D") (pinfunction "SHIELD_S3D") (pintype "passive"))
      (node (ref "J_USB") (pin "S3E") (pinfunction "SHIELD_S3E") (pintype "passive"))
      (node (ref "J_USB") (pin "S3F") (pinfunction "SHIELD_S3F") (pintype "passive"))
      (node (ref "J_USB") (pin "S3G") (pinfunction "SHIELD_S3G") (pintype "passive"))
      (node (ref "J_USB") (pin "S3H") (pinfunction "SHIELD_S3H") (pintype "passive"))
      (node (ref "J_USB") (pin "S3I") (pinfunction "SHIELD_S3I") (pintype "passive"))
      (node (ref "J_USB") (pin "S4") (pinfunction "SHIELD_S4") (pintype "passive"))
      (node (ref "J_USB") (pin "S4B") (pinfunction "SHIELD_S4B") (pintype "passive"))
      (node (ref "J_USB") (pin "S4C") (pinfunction "SHIELD_S4C") (pintype "passive"))
      (node (ref "J_USB") (pin "S4D") (pinfunction "SHIELD_S4D") (pintype "passive"))
      (node (ref "J_USB") (pin "S4E") (pinfunction "SHIELD_S4E") (pintype "passive"))
      (node (ref "J_USB") (pin "S4F") (pinfunction "SHIELD_S4F") (pintype "passive"))
      (node (ref "J_USB") (pin "S4G") (pinfunction "SHIELD_S4G") (pintype "passive"))
      (node (ref "J_USB") (pin "S4H") (pinfunction "SHIELD_S4H") (pintype "passive"))
      (node (ref "J_USB") (pin "S4I") (pinfunction "SHIELD_S4I") (pintype "passive"))
      (node (ref "LED_STATUS") (pin "C") (pinfunction "C_C") (pintype "passive"))
      (node (ref "Q_CW") (pin "2") (pinfunction "S_2") (pintype "passive"))
      (node (ref "Q_WW") (pin "2") (pinfunction "S_2") (pintype "passive"))
      (node (ref "R_CC1") (pin "2") (pinfunction "2_2") (pintype "passive"))
      (node (ref "R_CC2") (pin "2") (pinfunction "2_2") (pintype "passive"))
      (node (ref "R_FBB") (pin "2") (pinfunction "2_2") (pintype "passive"))
      (node (ref "R_PDC") (pin "2") (pinfunction "2_2") (pintype "passive"))
      (node (ref "R_PDW") (pin "2") (pinfunction "2_2") (pintype "passive"))
      (node (ref "R_Q1") (pin "2") (pinfunction "2_2") (pintype "passive"))
      (node (ref "SW_BOOT") (pin "3") (pinfunction "2_3") (pintype "passive"))
      (node (ref "SW_BOOT") (pin "4") (pinfunction "2_4") (pintype "passive"))
      (node (ref "SW_RST") (pin "3") (pinfunction "2_3") (pintype "passive"))
      (node (ref "SW_RST") (pin "4") (pinfunction "2_4") (pintype "passive"))
      (node (ref "TVS1") (pin "A") (pinfunction "A_A") (pintype "passive"))
      (node (ref "U_BUCK") (pin "1") (pinfunction "GND_1") (pintype "passive"))
      (node (ref "U_DRV") (pin "10") (pinfunction "PGND3_10") (pintype "power_in"))
      (node (ref "U_DRV") (pin "12") (pinfunction "COMPP_12") (pintype "input"))
      (node (ref "U_DRV") (pin "13") (pinfunction "COMPN_13") (pintype "input"))
      (node (ref "U_DRV") (pin "14") (pinfunction "GND_14") (pintype "power_in"))
      (node (ref "U_DRV") (pin "19") (pinfunction "~{COMPO}_19") (pintype "output"))
      (node (ref "U_DRV") (pin "20") (pinfunction "GND_20") (pintype "power_in"))
      (node (ref "U_DRV") (pin "28") (pinfunction "GND_28") (pintype "power_in"))
      (node (ref "U_DRV") (pin "29") (pinfunction "EXP_29") (pintype "power_in"))
      (node (ref "U_DRV") (pin "6") (pinfunction "PGND1_6") (pintype "power_in"))
      (node (ref "U_DRV") (pin "7") (pinfunction "PGND2_7") (pintype "power_in"))
      (node (ref "U_MCU") (pin "1") (pinfunction "GND_1") (pintype "power_in"))
      (node (ref "U_MCU") (pin "40") (pinfunction "GND_40") (pintype "power_in"))
      (node (ref "U_MCU") (pin "41_1") (pinfunction "GND_41_1") (pintype "power_in"))
      (node (ref "U_MCU") (pin "41_2") (pinfunction "GND_41_2") (pintype "power_in"))
      (node (ref "U_MCU") (pin "41_3") (pinfunction "GND_41_3") (pintype "power_in"))
      (node (ref "U_MCU") (pin "41_4") (pinfunction "GND_41_4") (pintype "power_in"))
      (node (ref "U_MCU") (pin "41_5") (pinfunction "GND_41_5") (pintype "power_in"))
      (node (ref "U_MCU") (pin "41_6") (pinfunction "GND_41_6") (pintype "power_in"))
      (node (ref "U_MCU") (pin "41_7") (pinfunction "GND_41_7") (pintype "power_in"))
      (node (ref "U_MCU") (pin "41_8") (pinfunction "GND_41_8") (pintype "power_in"))
      (node (ref "U_MCU") (pin "41_9") (pinfunction "GND_41_9") (pintype "power_in"))
    )
    (net (code "26") (name "/GW_G") (class "Default")
      (node (ref "Q_WW") (pin "1") (pinfunction "G_1") (pintype "passive"))
      (node (ref "R_GW") (pin "1") (pinfunction "1_1") (pintype "passive"))
      (node (ref "R_PDW") (pin "1") (pinfunction "1_1") (pintype "passive"))
    )
    (net (code "27") (name "/LEDCW") (class "Default")
      (node (ref "R_GC") (pin "2") (pinfunction "2_2") (pintype "passive"))
      (node (ref "U_MCU") (pin "20") (pinfunction "IO12_20") (pintype "bidirectional"))
    )
    (net (code "28") (name "/LEDC_D") (class "Default")
      (node (ref "D_CLC") (pin "A") (pinfunction "A_A") (pintype "passive"))
      (node (ref "J_LED") (pin "3") (pinfunction "C_3") (pintype "passive"))
      (node (ref "Q_CW") (pin "3") (pinfunction "D_3") (pintype "passive"))
    )
    (net (code "29") (name "/LEDWW") (class "Default")
      (node (ref "R_GW") (pin "2") (pinfunction "2_2") (pintype "passive"))
      (node (ref "U_MCU") (pin "19") (pinfunction "IO11_19") (pintype "bidirectional"))
    )
    (net (code "30") (name "/LEDW_D") (class "Default")
      (node (ref "D_CLW") (pin "A") (pinfunction "A_A") (pintype "passive"))
      (node (ref "J_LED") (pin "2") (pinfunction "W_2") (pintype "passive"))
      (node (ref "Q_WW") (pin "3") (pinfunction "D_3") (pintype "passive"))
    )
    (net (code "31") (name "/MOT_U") (class "Default")
      (node (ref "J_MOTOR") (pin "1") (pinfunction "U_1") (pintype "passive"))
      (node (ref "U_DRV") (pin "5") (pinfunction "OUT1_5") (pintype "output"))
    )
    (net (code "32") (name "/MOT_V") (class "Default")
      (node (ref "J_MOTOR") (pin "2") (pinfunction "V_2") (pintype "passive"))
      (node (ref "U_DRV") (pin "8") (pinfunction "OUT2_8") (pintype "output"))
    )
    (net (code "33") (name "/MOT_W") (class "Default")
      (node (ref "J_MOTOR") (pin "3") (pinfunction "W_3") (pintype "passive"))
      (node (ref "U_DRV") (pin "9") (pinfunction "OUT3_9") (pintype "output"))
    )
    (net (code "34") (name "/NFAULT") (class "Default")
      (node (ref "R_NFAULT") (pin "2") (pinfunction "2_2") (pintype "passive"))
      (node (ref "U_DRV") (pin "18") (pinfunction "~{FAULT}_18") (pintype "output"))
      (node (ref "U_MCU") (pin "9") (pinfunction "IO16_9") (pintype "bidirectional"))
    )
    (net (code "35") (name "/NRESET") (class "Default")
      (node (ref "R_NRESET") (pin "2") (pinfunction "2_2") (pintype "passive"))
      (node (ref "U_DRV") (pin "16") (pinfunction "~{RESET}_16") (pintype "input"))
    )
    (net (code "36") (name "/NSLEEP") (class "Default")
      (node (ref "R_NSLEEP") (pin "2") (pinfunction "2_2") (pintype "passive"))
      (node (ref "U_DRV") (pin "17") (pinfunction "~{SLEEP}_17") (pintype "input"))
      (node (ref "U_MCU") (pin "7") (pinfunction "IO7_7") (pintype "bidirectional"))
    )
    (net (code "37") (name "/P3V3") (class "Default")
      (node (ref "C_FF") (pin "1") (pinfunction "1_1") (pintype "passive"))
      (node (ref "C_MCU1") (pin "1") (pinfunction "1_1") (pintype "passive"))
      (node (ref "C_MCU2") (pin "1") (pinfunction "1_1") (pintype "passive"))
      (node (ref "C_MCU3") (pin "1") (pinfunction "1_1") (pintype "passive"))
      (node (ref "C_MCU4") (pin "1") (pinfunction "1_1") (pintype "passive"))
      (node (ref "C_MCU_BULK") (pin "1") (pinfunction "1_1") (pintype "passive"))
      (node (ref "C_OUT1") (pin "1") (pinfunction "1_1") (pintype "passive"))
      (node (ref "C_OUT2") (pin "1") (pinfunction "1_1") (pintype "passive"))
      (node (ref "C_SENS") (pin "1") (pinfunction "1_1") (pintype "passive"))
      (node (ref "D_MCU") (pin "C") (pinfunction "C_C") (pintype "passive"))
      (node (ref "J_EXP") (pin "1") (pinfunction "3V3_1") (pintype "passive"))
      (node (ref "J_PROG") (pin "1") (pinfunction "3V3_1") (pintype "passive"))
      (node (ref "J_SENSOR") (pin "1") (pinfunction "VCC_1") (pintype "passive"))
      (node (ref "L1") (pin "2") (pinfunction "2_2") (pintype "passive"))
      (node (ref "R_AZ_A") (pin "1") (pinfunction "1_1") (pintype "passive"))
      (node (ref "R_AZ_B") (pin "1") (pinfunction "1_1") (pintype "passive"))
      (node (ref "R_AZ_C") (pin "1") (pinfunction "1_1") (pintype "passive"))
      (node (ref "R_BOOT") (pin "1") (pinfunction "1_1") (pintype "passive"))
      (node (ref "R_EN") (pin "1") (pinfunction "1_1") (pintype "passive"))
      (node (ref "R_EN_DRV") (pin "1") (pinfunction "1_1") (pintype "passive"))
      (node (ref "R_FBT") (pin "1") (pinfunction "1_1") (pintype "passive"))
      (node (ref "R_NFAULT") (pin "1") (pinfunction "1_1") (pintype "passive"))
      (node (ref "R_NRESET") (pin "1") (pinfunction "1_1") (pintype "passive"))
      (node (ref "R_NSLEEP") (pin "1") (pinfunction "1_1") (pintype "passive"))
      (node (ref "U_MCU") (pin "2") (pinfunction "3V3_2") (pintype "power_in"))
    )
    (net (code "38") (name "/P24") (class "Default")
      (node (ref "C_IN1") (pin "1") (pinfunction "1_1") (pintype "passive"))
      (node (ref "C_IN2") (pin "1") (pinfunction "1_1") (pintype "passive"))
      (node (ref "C_IN_BULK") (pin "1") (pinfunction "1_1") (pintype "passive"))
      (node (ref "C_VCP") (pin "2") (pinfunction "2_2") (pintype "passive"))
      (node (ref "C_VM1") (pin "1") (pinfunction "1_1") (pintype "passive"))
      (node (ref "C_VM2") (pin "1") (pinfunction "1_1") (pintype "passive"))
      (node (ref "C_VM_BULK") (pin "1") (pinfunction "1_1") (pintype "passive"))
      (node (ref "D_CLC") (pin "C") (pinfunction "C_C") (pintype "passive"))
      (node (ref "D_CLW") (pin "C") (pinfunction "C_C") (pintype "passive"))
      (node (ref "D_OR_USB") (pin "C") (pinfunction "C_C") (pintype "passive"))
      (node (ref "D_Q1") (pin "C") (pinfunction "C_C") (pintype "passive"))
      (node (ref "J_LED") (pin "1") (pinfunction "VP_1") (pintype "passive"))
      (node (ref "Q1") (pin "2") (pinfunction "S_2") (pintype "passive"))
      (node (ref "R_ENB") (pin "1") (pinfunction "1_1") (pintype "passive"))
      (node (ref "TVS1") (pin "C") (pinfunction "C_C") (pintype "passive"))
      (node (ref "U_BUCK") (pin "3") (pinfunction "VIN_3") (pintype "passive"))
      (node (ref "U_DRV") (pin "11") (pinfunction "VM_11") (pintype "power_in"))
      (node (ref "U_DRV") (pin "4") (pinfunction "VM_4") (pintype "power_in"))
    )
    (net (code "39") (name "/P24_F") (class "Default")
      (node (ref "F1") (pin "2") (pinfunction "2_2") (pintype "passive"))
      (node (ref "Q1") (pin "3") (pinfunction "D_3") (pintype "passive"))
    )
    (net (code "40") (name "/P24_RAW") (class "Default")
      (node (ref "F1") (pin "1") (pinfunction "1_1") (pintype "passive"))
      (node (ref "J_PWR") (pin "1") (pinfunction "VP_1") (pintype "passive"))
    )
    (net (code "41") (name "/PWMA") (class "Default")
      (node (ref "U_DRV") (pin "27") (pinfunction "IN1_27") (pintype "input"))
      (node (ref "U_MCU") (pin "4") (pinfunction "IO4_4") (pintype "bidirectional"))
    )
    (net (code "42") (name "/PWMB") (class "Default")
      (node (ref "U_DRV") (pin "25") (pinfunction "IN2_25") (pintype "input"))
      (node (ref "U_MCU") (pin "5") (pinfunction "IO5_5") (pintype "bidirectional"))
    )
    (net (code "43") (name "/PWMC") (class "Default")
      (node (ref "U_DRV") (pin "23") (pinfunction "IN3_23") (pintype "input"))
      (node (ref "U_MCU") (pin "6") (pinfunction "IO6_6") (pintype "bidirectional"))
    )
    (net (code "44") (name "/Q1G") (class "Default")
      (node (ref "D_Q1") (pin "A") (pinfunction "A_A") (pintype "passive"))
      (node (ref "Q1") (pin "1") (pinfunction "G_1") (pintype "passive"))
      (node (ref "R_Q1") (pin "1") (pinfunction "1_1") (pintype "passive"))
    )
    (net (code "45") (name "/ROTA") (class "Default")
      (node (ref "J_KNOB") (pin "1") (pinfunction "A_1") (pintype "passive"))
      (node (ref "U_MCU") (pin "12") (pinfunction "IO8_12") (pintype "bidirectional"))
    )
    (net (code "46") (name "/ROTB") (class "Default")
      (node (ref "J_KNOB") (pin "2") (pinfunction "B_2") (pintype "passive"))
      (node (ref "U_MCU") (pin "17") (pinfunction "IO9_17") (pintype "bidirectional"))
    )
    (net (code "47") (name "/STAT") (class "Default")
      (node (ref "R_STATUS") (pin "1") (pinfunction "1_1") (pintype "passive"))
      (node (ref "U_MCU") (pin "23") (pinfunction "IO21_23") (pintype "bidirectional"))
    )
    (net (code "48") (name "/STAT_A") (class "Default")
      (node (ref "LED_STATUS") (pin "A") (pinfunction "A_A") (pintype "passive"))
      (node (ref "R_STATUS") (pin "2") (pinfunction "2_2") (pintype "passive"))
    )
    (net (code "49") (name "/SW") (class "Default")
      (node (ref "C_BOOT_B") (pin "2") (pinfunction "2_2") (pintype "passive"))
      (node (ref "L1") (pin "1") (pinfunction "1_1") (pintype "passive"))
      (node (ref "U_BUCK") (pin "2") (pinfunction "SW_2") (pintype "passive"))
    )
    (net (code "50") (name "/U0RXD") (class "Default")
      (node (ref "J_PROG") (pin "6") (pinfunction "RXD_6") (pintype "passive"))
      (node (ref "U_MCU") (pin "36") (pinfunction "RXD0_36") (pintype "bidirectional"))
    )
    (net (code "51") (name "/U0TXD") (class "Default")
      (node (ref "J_PROG") (pin "5") (pinfunction "TXD_5") (pintype "passive"))
      (node (ref "U_MCU") (pin "37") (pinfunction "TXD0_37") (pintype "bidirectional"))
    )
    (net (code "52") (name "/USBDM_RAW") (class "Default")
      (node (ref "D_USB") (pin "1") (pinfunction "I/O1_IN_1") (pintype "bidirectional"))
      (node (ref "D_USB") (pin "6") (pinfunction "I/O1_OUT_6") (pintype "bidirectional"))
      (node (ref "J_USB") (pin "A7") (pinfunction "DN1_A7") (pintype "bidirectional"))
      (node (ref "J_USB") (pin "B7") (pinfunction "DN2_B7") (pintype "bidirectional"))
      (node (ref "R_DM") (pin "1") (pinfunction "1_1") (pintype "passive"))
    )
    (net (code "53") (name "/USBDP_RAW") (class "Default")
      (node (ref "D_USB") (pin "3") (pinfunction "I/O2_IN_3") (pintype "bidirectional"))
      (node (ref "D_USB") (pin "4") (pinfunction "I/O2_OUT_4") (pintype "bidirectional"))
      (node (ref "J_USB") (pin "A6") (pinfunction "DP1_A6") (pintype "bidirectional"))
      (node (ref "J_USB") (pin "B6") (pinfunction "DP2_B6") (pintype "bidirectional"))
      (node (ref "R_DP") (pin "1") (pinfunction "1_1") (pintype "passive"))
    )
    (net (code "54") (name "/USB_DM_MCU") (class "Default")
      (node (ref "R_DM") (pin "2") (pinfunction "2_2") (pintype "passive"))
      (node (ref "U_MCU") (pin "13") (pinfunction "IO19_13") (pintype "bidirectional"))
    )
    (net (code "55") (name "/USB_DP_MCU") (class "Default")
      (node (ref "R_DP") (pin "2") (pinfunction "2_2") (pintype "passive"))
      (node (ref "U_MCU") (pin "14") (pinfunction "IO20_14") (pintype "bidirectional"))
    )
    (net (code "56") (name "/VBUS") (class "Default")
      (node (ref "C_VBUS") (pin "1") (pinfunction "1_1") (pintype "passive"))
      (node (ref "D_OR_USB") (pin "A") (pinfunction "A_A") (pintype "passive"))
      (node (ref "D_USB") (pin "5") (pinfunction "VBUS_5") (pintype "power_in"))
      (node (ref "J_USB") (pin "A4_B9") (pinfunction "VBUS_A4_B9") (pintype "power_in"))
      (node (ref "J_USB") (pin "B4_A9") (pinfunction "VBUS_B4_A9") (pintype "power_in"))
    )
    (net (code "57") (name "/VCP") (class "Default")
      (node (ref "C_VCP") (pin "1") (pinfunction "1_1") (pintype "passive"))
      (node (ref "U_DRV") (pin "3") (pinfunction "VCP_3") (pintype "power_in"))
    )
    (net (code "58") (name "unconnected-(J_USB-SBU1-PadA8)") (class "Default")
      (node (ref "J_USB") (pin "A8") (pinfunction "SBU1_A8") (pintype "bidirectional"))
    )
    (net (code "59") (name "unconnected-(J_USB-SBU2-PadB8)") (class "Default")
      (node (ref "J_USB") (pin "B8") (pinfunction "SBU2_B8") (pintype "bidirectional"))
    )
    (net (code "60") (name "unconnected-(U_DRV-NC-Pad21)") (class "Default")
      (node (ref "U_DRV") (pin "21") (pinfunction "NC_21") (pintype "no_connect"))
    )
    (net (code "61") (name "unconnected-(U_MCU-IO3-Pad15)") (class "Default")
      (node (ref "U_MCU") (pin "15") (pinfunction "IO3_15") (pintype "bidirectional"))
    )
    (net (code "62") (name "unconnected-(U_MCU-IO35-Pad28)") (class "Default")
      (node (ref "U_MCU") (pin "28") (pinfunction "IO35_28") (pintype "bidirectional"))
    )
    (net (code "63") (name "unconnected-(U_MCU-IO36-Pad29)") (class "Default")
      (node (ref "U_MCU") (pin "29") (pinfunction "IO36_29") (pintype "bidirectional"))
    )
    (net (code "64") (name "unconnected-(U_MCU-IO37-Pad30)") (class "Default")
      (node (ref "U_MCU") (pin "30") (pinfunction "IO37_30") (pintype "bidirectional"))
    )
    (net (code "65") (name "unconnected-(U_MCU-IO45-Pad26)") (class "Default")
      (node (ref "U_MCU") (pin "26") (pinfunction "IO45_26") (pintype "bidirectional"))
    )
    (net (code "66") (name "unconnected-(U_MCU-IO46-Pad16)") (class "Default")
      (node (ref "U_MCU") (pin "16") (pinfunction "IO46_16") (pintype "bidirectional"))
    )
    (net (code "67") (name "unconnected-(U_MCU-IO47-Pad24)") (class "Default")
      (node (ref "U_MCU") (pin "24") (pinfunction "IO47_24") (pintype "bidirectional"))
    )
    (net (code "68") (name "unconnected-(U_MCU-IO48-Pad25)") (class "Default")
      (node (ref "U_MCU") (pin "25") (pinfunction "IO48_25") (pintype "bidirectional"))
    )
  )
)
